# hri_hand_schematic.net
KiCad netlist of a schematic drawn in Altium Designer
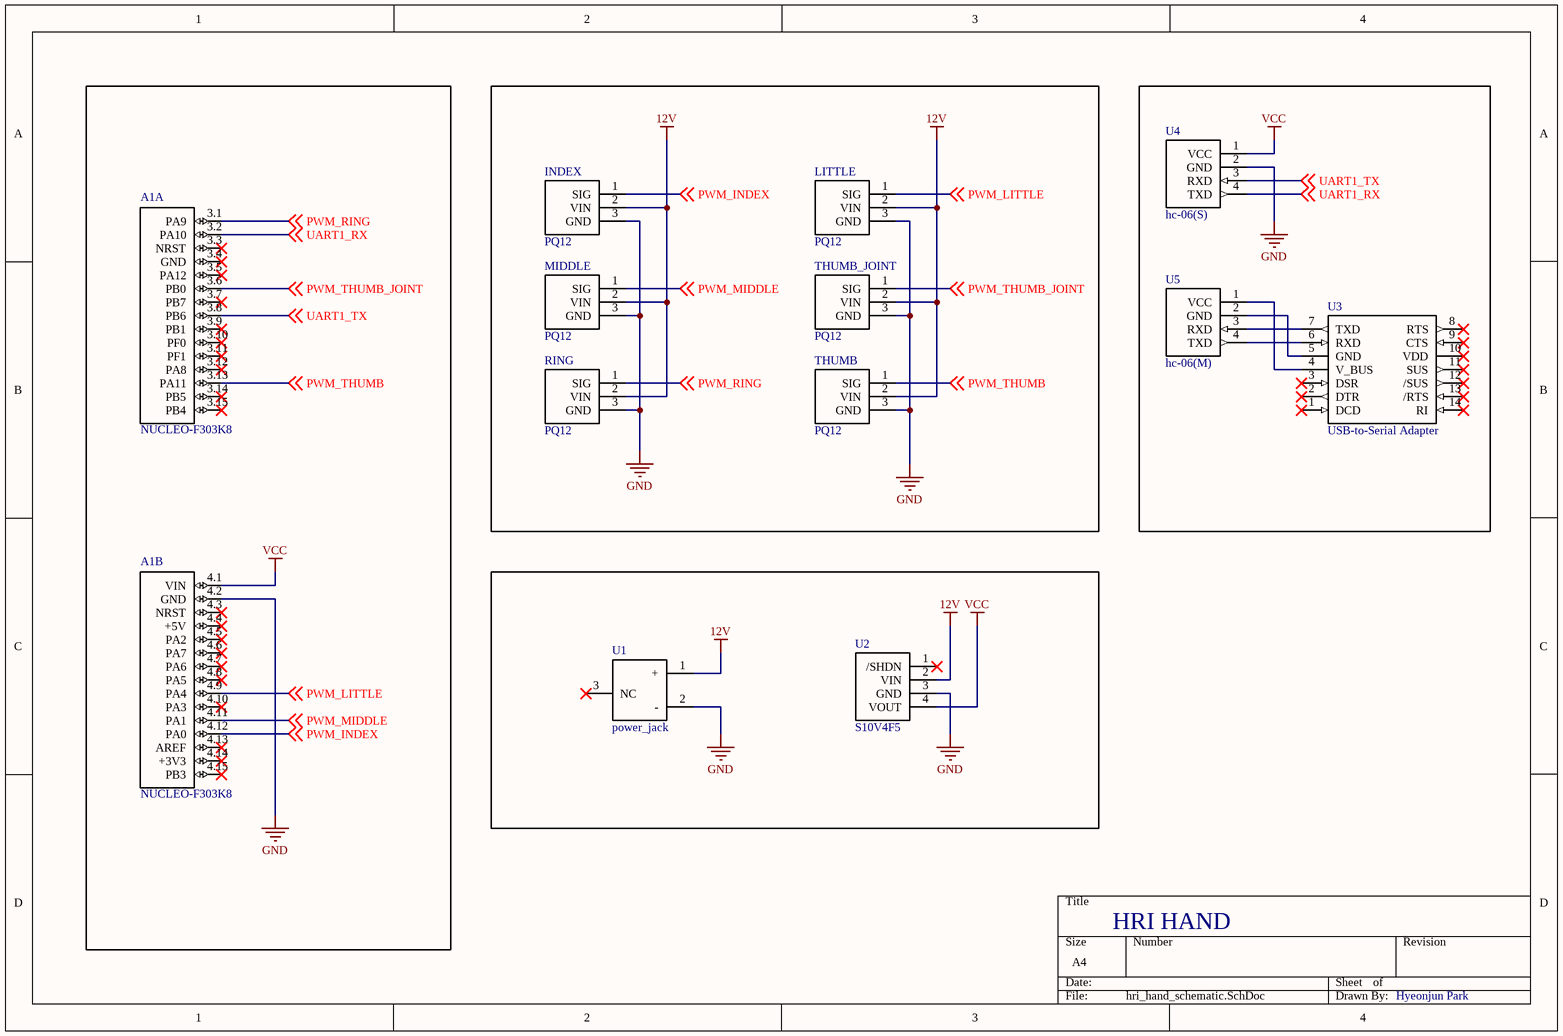
[diagram p0: hri_hand_schematic.SchDoc]

(export (version "E")
  (design (tool "Eeschema 10.0.6"))
  (components
    (comp (ref "A1")
      (value "NUCLEO-F303K8")
      (footprint "*MODULE_NUCLEO-F303K8_NUCLEO-F303K8(Primary)")
      (description "STM32 Nucleo-32 development board with STM32F303K8T6 MCU, supports Arduino connectivity")
      (fields (field (name "MF") "STMicroelectronics") (field (name "DIGI-KEY_PART_NUMBER") "497-15981-ND"))
      (libsource (lib "NUCLEO-F303K8") (part "NUCLEO-F303K8"))
    )
    (comp (ref "INDEX") (value "PQ12") (libsource (lib "NUCLEO-F303K8") (part "PQ12")))
    (comp (ref "LITTLE") (value "PQ12") (libsource (lib "NUCLEO-F303K8") (part "PQ12")))
    (comp (ref "MIDDLE") (value "PQ12") (libsource (lib "NUCLEO-F303K8") (part "PQ12")))
    (comp (ref "RING") (value "PQ12") (libsource (lib "NUCLEO-F303K8") (part "PQ12")))
    (comp (ref "THUMB") (value "PQ12") (libsource (lib "NUCLEO-F303K8") (part "PQ12")))
    (comp (ref "THUMB_JOINT") (value "PQ12") (libsource (lib "NUCLEO-F303K8") (part "PQ12")))
    (comp (ref "U1") (value "power_jack") (libsource (lib "NUCLEO-F303K8") (part "power_jack")))
    (comp (ref "U2") (value "S10V4F5") (libsource (lib "NUCLEO-F303K8") (part "S10V4F5")))
    (comp (ref "U3")
      (value "USB-to-Serial Adapter")
      (libsource (lib "NUCLEO-F303K8") (part "USB-to-Serial Adapter"))
    )
    (comp (ref "U4") (value "hc-06(S)") (libsource (lib "NUCLEO-F303K8") (part "hc-06")))
    (comp (ref "U5") (value "hc-06(M)") (libsource (lib "NUCLEO-F303K8") (part "hc-06")))
  )
  (nets
    (net (code "1") (name "12V") (class "Default")
      (node (ref "INDEX") (pin "2") (pinfunction "VIN_2") (pintype "power_in"))
      (node (ref "LITTLE") (pin "2") (pinfunction "VIN_2") (pintype "power_in"))
      (node (ref "MIDDLE") (pin "2") (pinfunction "VIN_2") (pintype "power_in"))
      (node (ref "RING") (pin "2") (pinfunction "VIN_2") (pintype "power_in"))
      (node (ref "THUMB") (pin "2") (pinfunction "VIN_2") (pintype "power_in"))
      (node (ref "THUMB_JOINT") (pin "2") (pinfunction "VIN_2") (pintype "power_in"))
      (node (ref "U1") (pin "1") (pinfunction "+_1") (pintype "power_in"))
      (node (ref "U2") (pin "2") (pinfunction "VIN_2") (pintype "power_in"))
    )
    (net (code "2") (name "GND") (class "Default")
      (node (ref "A1") (pin "4.2") (pinfunction "GND_4.2") (pintype "bidirectional"))
      (node (ref "INDEX") (pin "3") (pinfunction "GND_3") (pintype "power_in"))
      (node (ref "LITTLE") (pin "3") (pinfunction "GND_3") (pintype "power_in"))
      (node (ref "MIDDLE") (pin "3") (pinfunction "GND_3") (pintype "power_in"))
      (node (ref "RING") (pin "3") (pinfunction "GND_3") (pintype "power_in"))
      (node (ref "THUMB") (pin "3") (pinfunction "GND_3") (pintype "power_in"))
      (node (ref "THUMB_JOINT") (pin "3") (pinfunction "GND_3") (pintype "power_in"))
      (node (ref "U1") (pin "2") (pinfunction "-_2") (pintype "power_in"))
      (node (ref "U2") (pin "3") (pinfunction "GND_3") (pintype "power_in"))
      (node (ref "U4") (pin "2") (pinfunction "GND_2") (pintype "power_in"))
    )
    (net (code "3") (name "Net-(U3-GND)") (class "Default")
      (node (ref "U3") (pin "5") (pinfunction "GND_5") (pintype "power_in"))
      (node (ref "U5") (pin "2") (pinfunction "GND_2") (pintype "power_in"))
    )
    (net (code "4") (name "Net-(U3-RXD)") (class "Default")
      (node (ref "U3") (pin "6") (pinfunction "RXD_6") (pintype "input"))
      (node (ref "U5") (pin "4") (pinfunction "TXD_4") (pintype "output"))
    )
    (net (code "5") (name "Net-(U3-TXD)") (class "Default")
      (node (ref "U3") (pin "7") (pinfunction "TXD_7") (pintype "output"))
      (node (ref "U5") (pin "3") (pinfunction "RXD_3") (pintype "input"))
    )
    (net (code "6") (name "Net-(U3-V_BUS)") (class "Default")
      (node (ref "U3") (pin "4") (pinfunction "V_BUS_4") (pintype "power_in"))
      (node (ref "U5") (pin "1") (pinfunction "VCC_1") (pintype "power_in"))
    )
    (net (code "7") (name "PWM_INDEX") (class "Default")
      (node (ref "A1") (pin "4.12") (pinfunction "PA0_4.12") (pintype "bidirectional"))
      (node (ref "INDEX") (pin "1") (pinfunction "SIG_1") (pintype "power_in"))
    )
    (net (code "8") (name "PWM_LITTLE") (class "Default")
      (node (ref "A1") (pin "4.9") (pinfunction "PA4_4.9") (pintype "bidirectional"))
      (node (ref "LITTLE") (pin "1") (pinfunction "SIG_1") (pintype "power_in"))
    )
    (net (code "9") (name "PWM_MIDDLE") (class "Default")
      (node (ref "A1") (pin "4.11") (pinfunction "PA1_4.11") (pintype "bidirectional"))
      (node (ref "MIDDLE") (pin "1") (pinfunction "SIG_1") (pintype "power_in"))
    )
    (net (code "10") (name "PWM_RING") (class "Default")
      (node (ref "A1") (pin "3.1") (pinfunction "PA9_3.1") (pintype "bidirectional"))
      (node (ref "RING") (pin "1") (pinfunction "SIG_1") (pintype "power_in"))
    )
    (net (code "11") (name "PWM_THUMB") (class "Default")
      (node (ref "A1") (pin "3.13") (pinfunction "PA11_3.13") (pintype "bidirectional"))
      (node (ref "THUMB") (pin "1") (pinfunction "SIG_1") (pintype "power_in"))
    )
    (net (code "12") (name "PWM_THUMB_JOINT") (class "Default")
      (node (ref "A1") (pin "3.6") (pinfunction "PB0_3.6") (pintype "bidirectional"))
      (node (ref "THUMB_JOINT") (pin "1") (pinfunction "SIG_1") (pintype "power_in"))
    )
    (net (code "13") (name "UART1_RX") (class "Default")
      (node (ref "A1") (pin "3.2") (pinfunction "PA10_3.2") (pintype "bidirectional"))
      (node (ref "U4") (pin "4") (pinfunction "TXD_4") (pintype "output"))
    )
    (net (code "14") (name "UART1_TX") (class "Default")
      (node (ref "A1") (pin "3.8") (pinfunction "PB6_3.8") (pintype "bidirectional"))
      (node (ref "U4") (pin "3") (pinfunction "RXD_3") (pintype "input"))
    )
    (net (code "15") (name "VCC") (class "Default")
      (node (ref "A1") (pin "4.1") (pinfunction "VIN_4.1") (pintype "bidirectional"))
      (node (ref "U2") (pin "4") (pinfunction "VOUT_4") (pintype "power_in"))
      (node (ref "U4") (pin "1") (pinfunction "VCC_1") (pintype "power_in"))
    )
    (net (code "16") (name "unconnected-(A1A-GND-Pad3.4)") (class "Default")
      (node (ref "A1") (pin "3.4") (pinfunction "GND_3.4") (pintype "bidirectional+no_connect"))
    )
    (net (code "17") (name "unconnected-(A1A-NRST-Pad3.3)") (class "Default")
      (node (ref "A1") (pin "3.3") (pinfunction "NRST_3.3") (pintype "bidirectional+no_connect"))
    )
    (net (code "18") (name "unconnected-(A1A-PA8-Pad3.12)") (class "Default")
      (node (ref "A1") (pin "3.12") (pinfunction "PA8_3.12") (pintype "bidirectional+no_connect"))
    )
    (net (code "19") (name "unconnected-(A1A-PA12-Pad3.5)") (class "Default")
      (node (ref "A1") (pin "3.5") (pinfunction "PA12_3.5") (pintype "bidirectional+no_connect"))
    )
    (net (code "20") (name "unconnected-(A1A-PB1-Pad3.9)") (class "Default")
      (node (ref "A1") (pin "3.9") (pinfunction "PB1_3.9") (pintype "bidirectional+no_connect"))
    )
    (net (code "21") (name "unconnected-(A1A-PB4-Pad3.15)") (class "Default")
      (node (ref "A1") (pin "3.15") (pinfunction "PB4_3.15") (pintype "bidirectional+no_connect"))
    )
    (net (code "22") (name "unconnected-(A1A-PB5-Pad3.14)") (class "Default")
      (node (ref "A1") (pin "3.14") (pinfunction "PB5_3.14") (pintype "bidirectional+no_connect"))
    )
    (net (code "23") (name "unconnected-(A1A-PB7-Pad3.7)") (class "Default")
      (node (ref "A1") (pin "3.7") (pinfunction "PB7_3.7") (pintype "bidirectional+no_connect"))
    )
    (net (code "24") (name "unconnected-(A1A-PF0-Pad3.10)") (class "Default")
      (node (ref "A1") (pin "3.10") (pinfunction "PF0_3.10") (pintype "bidirectional+no_connect"))
    )
    (net (code "25") (name "unconnected-(A1A-PF1-Pad3.11)") (class "Default")
      (node (ref "A1") (pin "3.11") (pinfunction "PF1_3.11") (pintype "bidirectional+no_connect"))
    )
    (net (code "26") (name "unconnected-(A1B-+3V3-Pad4.14)") (class "Default")
      (node (ref "A1") (pin "4.14") (pinfunction "+3V3_4.14") (pintype "bidirectional+no_connect"))
    )
    (net (code "27") (name "unconnected-(A1B-+5V-Pad4.4)") (class "Default")
      (node (ref "A1") (pin "4.4") (pinfunction "+5V_4.4") (pintype "bidirectional+no_connect"))
    )
    (net (code "28") (name "unconnected-(A1B-AREF-Pad4.13)") (class "Default")
      (node (ref "A1") (pin "4.13") (pinfunction "AREF_4.13") (pintype "bidirectional+no_connect"))
    )
    (net (code "29") (name "unconnected-(A1B-NRST-Pad4.3)") (class "Default")
      (node (ref "A1") (pin "4.3") (pinfunction "NRST_4.3") (pintype "bidirectional+no_connect"))
    )
    (net (code "30") (name "unconnected-(A1B-PA2-Pad4.5)") (class "Default")
      (node (ref "A1") (pin "4.5") (pinfunction "PA2_4.5") (pintype "bidirectional+no_connect"))
    )
    (net (code "31") (name "unconnected-(A1B-PA3-Pad4.10)") (class "Default")
      (node (ref "A1") (pin "4.10") (pinfunction "PA3_4.10") (pintype "bidirectional+no_connect"))
    )
    (net (code "32") (name "unconnected-(A1B-PA5-Pad4.8)") (class "Default")
      (node (ref "A1") (pin "4.8") (pinfunction "PA5_4.8") (pintype "bidirectional+no_connect"))
    )
    (net (code "33") (name "unconnected-(A1B-PA6-Pad4.7)") (class "Default")
      (node (ref "A1") (pin "4.7") (pinfunction "PA6_4.7") (pintype "bidirectional+no_connect"))
    )
    (net (code "34") (name "unconnected-(A1B-PA7-Pad4.6)") (class "Default")
      (node (ref "A1") (pin "4.6") (pinfunction "PA7_4.6") (pintype "bidirectional+no_connect"))
    )
    (net (code "35") (name "unconnected-(A1B-PB3-Pad4.15)") (class "Default")
      (node (ref "A1") (pin "4.15") (pinfunction "PB3_4.15") (pintype "bidirectional+no_connect"))
    )
    (net (code "36") (name "unconnected-(U1-NC-Pad3)") (class "Default")
      (node (ref "U1") (pin "3") (pinfunction "NC_3") (pintype "power_in+no_connect"))
    )
    (net (code "37") (name "unconnected-(U2-{slash}SHDN-Pad1)") (class "Default")
      (node (ref "U2") (pin "1") (pinfunction "/SHDN_1") (pintype "power_in+no_connect"))
    )
    (net (code "38") (name "unconnected-(U3-CTS-Pad9)") (class "Default")
      (node (ref "U3") (pin "9") (pinfunction "CTS_9") (pintype "input+no_connect"))
    )
    (net (code "39") (name "unconnected-(U3-DCD-Pad1)") (class "Default")
      (node (ref "U3") (pin "1") (pinfunction "DCD_1") (pintype "input+no_connect"))
    )
    (net (code "40") (name "unconnected-(U3-DSR-Pad3)") (class "Default")
      (node (ref "U3") (pin "3") (pinfunction "DSR_3") (pintype "input+no_connect"))
    )
    (net (code "41") (name "unconnected-(U3-DTR-Pad2)") (class "Default")
      (node (ref "U3") (pin "2") (pinfunction "DTR_2") (pintype "output+no_connect"))
    )
    (net (code "42") (name "unconnected-(U3-RI-Pad14)") (class "Default")
      (node (ref "U3") (pin "14") (pinfunction "RI_14") (pintype "input+no_connect"))
    )
    (net (code "43") (name "unconnected-(U3-RTS-Pad8)") (class "Default")
      (node (ref "U3") (pin "8") (pinfunction "RTS_8") (pintype "output+no_connect"))
    )
    (net (code "44") (name "unconnected-(U3-SUS-Pad11)") (class "Default")
      (node (ref "U3") (pin "11") (pinfunction "SUS_11") (pintype "output+no_connect"))
    )
    (net (code "45") (name "unconnected-(U3-VDD-Pad10)") (class "Default")
      (node (ref "U3") (pin "10") (pinfunction "VDD_10") (pintype "power_in+no_connect"))
    )
    (net (code "46") (name "unconnected-(U3-{slash}RTS-Pad13)") (class "Default")
      (node (ref "U3") (pin "13") (pinfunction "/RTS_13") (pintype "input+no_connect"))
    )
    (net (code "47") (name "unconnected-(U3-{slash}SUS-Pad12)") (class "Default")
      (node (ref "U3") (pin "12") (pinfunction "/SUS_12") (pintype "output+no_connect"))
    )
  )
)
